# untitled.net
KiCad netlist of a schematic drawn in EAGLE
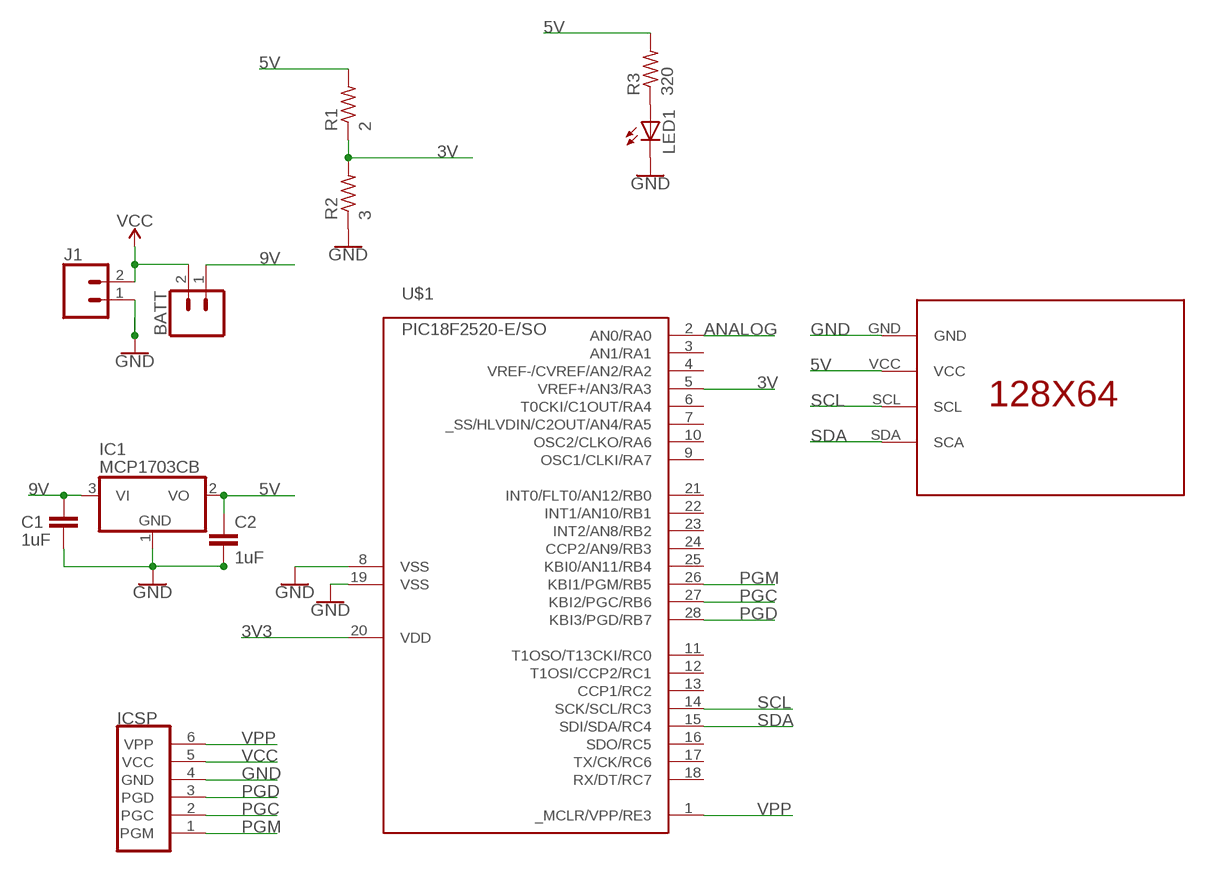
[diagram p0: schematic, sheet 1]
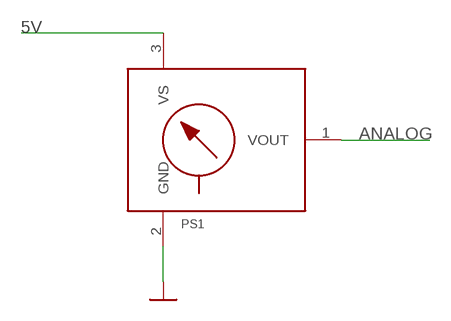
[diagram p1: schematic, sheet 2]

(export (version "E")
  (design (tool "Eeschema 10.0.6"))
  (components
    (comp (ref "BATT")
      (value "CONN_02")
      (footprint "eagle-import:1X02")
      (libsource (lib "eagle-import") (part "CONN_02"))
    )
    (comp (ref "C1")
      (value "1uF")
      (footprint "eagle-import:0805")
      (libsource (lib "eagle-import") (part "CAPACITOR-N0805"))
    )
    (comp (ref "C2")
      (value "1uF")
      (footprint "eagle-import:0805")
      (libsource (lib "eagle-import") (part "CAPACITOR-N0805"))
    )
    (comp (ref "IC1")
      (value "MCP1703CB")
      (footprint "eagle-import:SOT23")
      (libsource (lib "eagle-import") (part "MCP1703CB"))
    )
    (comp (ref "ICSP")
      (value "PIC_ICSP_6_PIN")
      (footprint "eagle-import:MOLEX-1X6")
      (libsource (lib "eagle-import") (part "PIC_ICSP_6_PIN"))
    )
    (comp (ref "J1")
      (value "CONN_02")
      (footprint "eagle-import:1X02")
      (libsource (lib "eagle-import") (part "CONN_02"))
    )
    (comp (ref "LED1")
      (value "LEDCHIP-LED0805")
      (footprint "eagle-import:CHIP-LED0805")
      (libsource (lib "eagle-import") (part "LEDCHIP-LED0805"))
    )
    (comp (ref "R1")
      (value "2")
      (footprint "eagle-import:R0805")
      (libsource (lib "eagle-import") (part "R-US_R0805"))
    )
    (comp (ref "R2")
      (value "3")
      (footprint "eagle-import:R0805")
      (libsource (lib "eagle-import") (part "R-US_R0805"))
    )
    (comp (ref "R3")
      (value "320")
      (footprint "eagle-import:R0805")
      (libsource (lib "eagle-import") (part "R-US_R0805"))
    )
    (comp (ref "U$1")
      (value "PIC18F2520-E/SO")
      (footprint "eagle-import:SO-28W")
      (libsource (lib "eagle-import") (part "PIC182520-E/SOF"))
    )
    (comp (ref "U$2")
      (value "128_64_OLED_SPI")
      (footprint "eagle-import:128_64_OLED_SPI")
      (libsource (lib "eagle-import") (part "128_64_OLED_SPI"))
    )
    (comp (ref "PS1")
      (value "MPX-867B-H")
      (footprint "eagle-import:867B-H")
      (libsource (lib "eagle-import") (part "MPX-867B-H"))
    )
  )
  (nets
    (net (code "1") (name "3V") (class "Default")
      (node (ref "R1") (pin "1") (pinfunction "1_1") (pintype "passive"))
      (node (ref "R2") (pin "2") (pinfunction "2_2") (pintype "passive"))
      (node (ref "U$1") (pin "5") (pinfunction "VREF+/AN3/RA3_5") (pintype "bidirectional"))
    )
    (net (code "2") (name "3V3") (class "Default")
      (node (ref "U$1") (pin "20") (pinfunction "VDD_20") (pintype "power_in"))
    )
    (net (code "3") (name "5V") (class "Default")
      (node (ref "C2") (pin "1") (pinfunction "1_1") (pintype "passive"))
      (node (ref "IC1") (pin "2") (pinfunction "VO_2") (pintype "passive"))
      (node (ref "PS1") (pin "3") (pinfunction "VS_3") (pintype "power_in"))
      (node (ref "R1") (pin "2") (pinfunction "2_2") (pintype "passive"))
      (node (ref "R3") (pin "2") (pinfunction "2_2") (pintype "passive"))
      (node (ref "U$2") (pin "VCC") (pinfunction "VCC_VCC") (pintype "bidirectional"))
    )
    (net (code "4") (name "9V") (class "Default")
      (node (ref "BATT") (pin "1") (pinfunction "1_1") (pintype "passive"))
      (node (ref "C1") (pin "1") (pinfunction "1_1") (pintype "passive"))
      (node (ref "IC1") (pin "3") (pinfunction "VI_3") (pintype "input"))
    )
    (net (code "5") (name "ANALOG") (class "Default")
      (node (ref "PS1") (pin "1") (pinfunction "VOUT_1") (pintype "output"))
      (node (ref "U$1") (pin "2") (pinfunction "AN0/RA0_2") (pintype "bidirectional"))
    )
    (net (code "6") (name "GND") (class "Default")
      (node (ref "C1") (pin "2") (pinfunction "2_2") (pintype "passive"))
      (node (ref "C2") (pin "2") (pinfunction "2_2") (pintype "passive"))
      (node (ref "IC1") (pin "1") (pinfunction "GND_1") (pintype "passive"))
      (node (ref "ICSP") (pin "4") (pinfunction "GND_4") (pintype "power_in"))
      (node (ref "J1") (pin "1") (pinfunction "1_1") (pintype "passive"))
      (node (ref "LED1") (pin "C") (pinfunction "C_C") (pintype "passive"))
      (node (ref "PS1") (pin "2") (pinfunction "GND_2") (pintype "power_in"))
      (node (ref "R2") (pin "1") (pinfunction "1_1") (pintype "passive"))
      (node (ref "U$1") (pin "19") (pinfunction "VSS_19") (pintype "power_in"))
      (node (ref "U$1") (pin "8") (pinfunction "VSS_8") (pintype "power_in"))
      (node (ref "U$2") (pin "GND") (pinfunction "GND_GND") (pintype "bidirectional"))
    )
    (net (code "7") (name "Net-(LED1-PadA)") (class "Default")
      (node (ref "LED1") (pin "A") (pinfunction "A_A") (pintype "passive"))
      (node (ref "R3") (pin "1") (pinfunction "1_1") (pintype "passive"))
    )
    (net (code "8") (name "PGC") (class "Default")
      (node (ref "ICSP") (pin "2") (pinfunction "PGC_2") (pintype "bidirectional"))
      (node (ref "U$1") (pin "27") (pinfunction "KBI2/PGC/RB6_27") (pintype "bidirectional"))
    )
    (net (code "9") (name "PGD") (class "Default")
      (node (ref "ICSP") (pin "3") (pinfunction "PGD_3") (pintype "bidirectional"))
      (node (ref "U$1") (pin "28") (pinfunction "KBI3/PGD/RB7_28") (pintype "bidirectional"))
    )
    (net (code "10") (name "PGM") (class "Default")
      (node (ref "ICSP") (pin "1") (pinfunction "PGM_1") (pintype "bidirectional"))
      (node (ref "U$1") (pin "26") (pinfunction "KBI1/PGM/RB5_26") (pintype "bidirectional"))
    )
    (net (code "11") (name "SCL") (class "Default")
      (node (ref "U$1") (pin "14") (pinfunction "SCK/SCL/RC3_14") (pintype "bidirectional"))
      (node (ref "U$2") (pin "SCL") (pinfunction "SCL_SCL") (pintype "bidirectional"))
    )
    (net (code "12") (name "SDA") (class "Default")
      (node (ref "U$1") (pin "15") (pinfunction "SDI/SDA/RC4_15") (pintype "bidirectional"))
      (node (ref "U$2") (pin "SDA") (pinfunction "SCA_SDA") (pintype "bidirectional"))
    )
    (net (code "13") (name "VCC") (class "Default")
      (node (ref "BATT") (pin "2") (pinfunction "2_2") (pintype "passive"))
      (node (ref "ICSP") (pin "5") (pinfunction "VCC_5") (pintype "power_in"))
      (node (ref "J1") (pin "2") (pinfunction "2_2") (pintype "passive"))
    )
    (net (code "14") (name "VPP") (class "Default")
      (node (ref "ICSP") (pin "6") (pinfunction "VPP_6") (pintype "bidirectional"))
      (node (ref "U$1") (pin "1") (pinfunction "_MCLR/VPP/RE3_1") (pintype "input"))
    )
    (net (code "15") (name "unconnected-(PS1-NC-Pad4)") (class "Default")
      (node (ref "PS1") (pin "4") (pinfunction "NC_4") (pintype "no_connect"))
    )
    (net (code "16") (name "unconnected-(PS1-NC-Pad5)") (class "Default")
      (node (ref "PS1") (pin "5") (pinfunction "NC_5") (pintype "no_connect"))
    )
    (net (code "17") (name "unconnected-(PS1-NC-Pad6)") (class "Default")
      (node (ref "PS1") (pin "6") (pinfunction "NC_6") (pintype "no_connect"))
    )
    (net (code "18") (name "unconnected-(U$1-AN1{slash}RA1-Pad3)") (class "Default")
      (node (ref "U$1") (pin "3") (pinfunction "AN1/RA1_3") (pintype "bidirectional"))
    )
    (net (code "19") (name "unconnected-(U$1-CCP1{slash}RC2-Pad13)") (class "Default")
      (node (ref "U$1") (pin "13") (pinfunction "CCP1/RC2_13") (pintype "bidirectional"))
    )
    (net (code "20") (name "unconnected-(U$1-CCP2{slash}AN9{slash}RB3-Pad24)") (class "Default")
      (node (ref "U$1") (pin "24") (pinfunction "CCP2/AN9/RB3_24") (pintype "bidirectional"))
    )
    (net (code "21") (name "unconnected-(U$1-INT0{slash}FLT0{slash}AN12{slash}RB0-Pad21)") (class "Default")
      (node (ref "U$1") (pin "21") (pinfunction "INT0/FLT0/AN12/RB0_21") (pintype "bidirectional"))
    )
    (net (code "22") (name "unconnected-(U$1-INT1{slash}AN10{slash}RB1-Pad22)") (class "Default")
      (node (ref "U$1") (pin "22") (pinfunction "INT1/AN10/RB1_22") (pintype "bidirectional"))
    )
    (net (code "23") (name "unconnected-(U$1-INT2{slash}AN8{slash}RB2-Pad23)") (class "Default")
      (node (ref "U$1") (pin "23") (pinfunction "INT2/AN8/RB2_23") (pintype "bidirectional"))
    )
    (net (code "24") (name "unconnected-(U$1-KBI0{slash}AN11{slash}RB4-Pad25)") (class "Default")
      (node (ref "U$1") (pin "25") (pinfunction "KBI0/AN11/RB4_25") (pintype "bidirectional"))
    )
    (net (code "25") (name "unconnected-(U$1-OSC1{slash}CLKI{slash}RA7-Pad9)") (class "Default")
      (node (ref "U$1") (pin "9") (pinfunction "OSC1/CLKI/RA7_9") (pintype "bidirectional"))
    )
    (net (code "26") (name "unconnected-(U$1-OSC2{slash}CLKO{slash}RA6-Pad10)") (class "Default")
      (node (ref "U$1") (pin "10") (pinfunction "OSC2/CLKO/RA6_10") (pintype "bidirectional"))
    )
    (net (code "27") (name "unconnected-(U$1-RX{slash}DT{slash}RC7-Pad18)") (class "Default")
      (node (ref "U$1") (pin "18") (pinfunction "RX/DT/RC7_18") (pintype "bidirectional"))
    )
    (net (code "28") (name "unconnected-(U$1-SDO{slash}RC5-Pad16)") (class "Default")
      (node (ref "U$1") (pin "16") (pinfunction "SDO/RC5_16") (pintype "bidirectional"))
    )
    (net (code "29") (name "unconnected-(U$1-T0CKI{slash}C1OUT{slash}RA4-Pad6)") (class "Default")
      (node (ref "U$1") (pin "6") (pinfunction "T0CKI/C1OUT/RA4_6") (pintype "bidirectional"))
    )
    (net (code "30") (name "unconnected-(U$1-T1OSI{slash}CCP2{slash}RC1-Pad12)") (class "Default")
      (node (ref "U$1") (pin "12") (pinfunction "T1OSI/CCP2/RC1_12") (pintype "bidirectional"))
    )
    (net (code "31") (name "unconnected-(U$1-T1OSO{slash}T13CKI{slash}RC0-Pad11)") (class "Default")
      (node (ref "U$1") (pin "11") (pinfunction "T1OSO/T13CKI/RC0_11") (pintype "bidirectional"))
    )
    (net (code "32") (name "unconnected-(U$1-TX{slash}CK{slash}RC6-Pad17)") (class "Default")
      (node (ref "U$1") (pin "17") (pinfunction "TX/CK/RC6_17") (pintype "bidirectional"))
    )
    (net (code "33") (name "unconnected-(U$1-VREF-{slash}CVREF{slash}AN2{slash}RA2-Pad4)") (class "Default")
      (node (ref "U$1") (pin "4") (pinfunction "VREF-/CVREF/AN2/RA2_4") (pintype "bidirectional"))
    )
    (net (code "34") (name "unconnected-(U$1-_SS{slash}HLVDIN{slash}C2OUT{slash}AN4{slash}RA5-Pad7)") (class "Default")
      (node (ref "U$1") (pin "7") (pinfunction "_SS/HLVDIN/C2OUT/AN4/RA5_7") (pintype "bidirectional"))
    )
  )
)
